# Power_Tree.net
KiCad netlist of a schematic drawn in Altium Designer
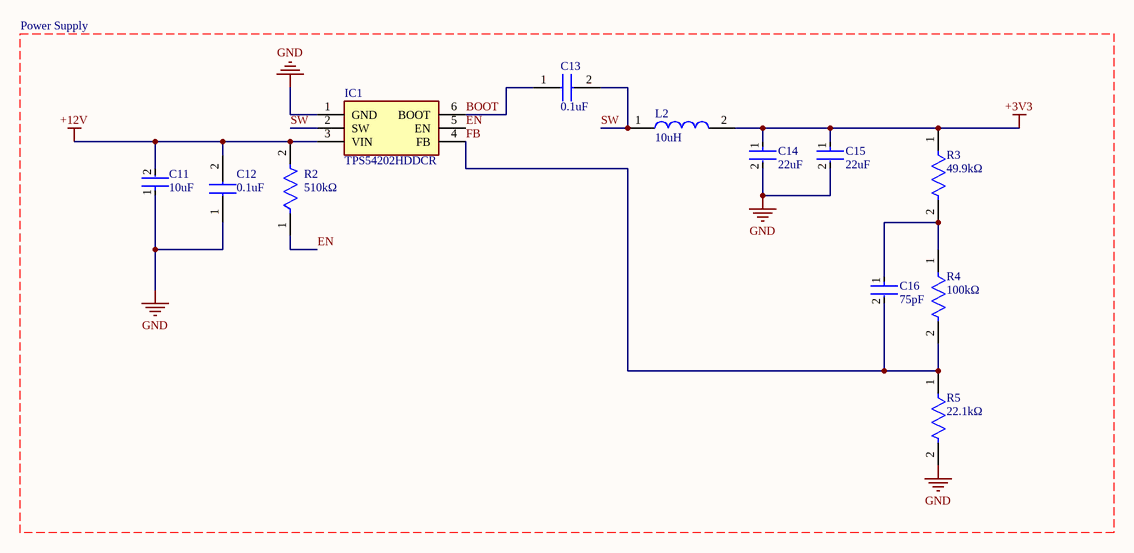
[diagram p0: Power_Tree.SchDoc]

(export (version "E")
  (design (tool "Eeschema 10.0.6"))
  (components
    (comp (ref "C11")
      (value "10uF")
      (footprint "FP-GRT31C-0_2-IPC_A")
      (description "Multi-Layer Ceramic Capacitor 10uF 50V X5R ±10% 1206 Emboss T/R")
      (fields (field (name "TOLERANCE") "10%"))
      (libsource (lib "Altium Content Vault") (part "02cd4be3c70576c341d710602a673aa"))
    )
    (comp (ref "C12")
      (value "0.1uF")
      (footprint "SamacSys:C0805")
      (description "Capacitor")
      (fields
        (field (name "MANUFACTURER_PART_NUMBER") "C0805C104K6RACTU")
        (field (name "MOUSER PART NUMBER") "80-C0805C104K6R")
      )
      (libsource (lib "*") (part "C0805C104K6RACTU"))
    )
    (comp (ref "C13")
      (value "0.1uF")
      (footprint "SamacSys:C0805")
      (description "Capacitor")
      (fields
        (field (name "MANUFACTURER_PART_NUMBER") "C0805C104K6RACTU")
        (field (name "MOUSER PART NUMBER") "80-C0805C104K6R")
      )
      (libsource (lib "*") (part "C0805C104K6RACTU"))
    )
    (comp (ref "C14")
      (value "22uF")
      (footprint "FP-1206-L_3_2_0_3-W_1_6_0-IPC_A")
      (description "None")
      (fields (field (name "TOLERANCE") "20%"))
      (libsource (lib "Altium Content Vault") (part "11868f565c42a9108669ba33697ecf6"))
    )
    (comp (ref "C15")
      (value "22uF")
      (footprint "FP-1206-L_3_2_0_3-W_1_6_0-IPC_A")
      (description "None")
      (fields (field (name "TOLERANCE") "20%"))
      (libsource (lib "Altium Content Vault") (part "11868f565c42a9108669ba33697ecf6"))
    )
    (comp (ref "C16")
      (value "75pF")
      (footprint "FP-C1206C-EB-MFG")
      (description "CAP CER 75PF 50V NP0 1206")
      (fields (field (name "TOLERANCE") "0.05") (field (name "MANUFACTURER PART NUMBER") "C1206C750J5GACTU"))
      (libsource (lib "Altium Content Vault") (part "b4654b650e69147ec39a6b967a45e02"))
    )
    (comp (ref "IC1")
      (value "TPS54202HDDCR")
      (footprint "SamacSys:SOT95P280X110-6N")
      (description "Integrated Circuit")
      (fields (field (name "MOUSER PART NUMBER") "595-TPS54202HDDCR"))
      (libsource (lib "*") (part "TPS54202HDDCR"))
    )
    (comp (ref "L2")
      (value "10uH")
      (footprint "SamacSys:SRN6045_1")
      (description "Inductor")
      (fields
        (field (name "MANUFACTURER_PART_NUMBER") "SRN6045-100M")
        (field (name "MOUSER PART NUMBER") "652-SRN6045-100M")
      )
      (libsource (lib "*") (part "SRN6045-100M"))
    )
    (comp (ref "R2")
      (value "510kΩ")
      (footprint "FP-CRCW0805-e3-IPC_B")
      (description "RES Thick Film, 510kΩ, 1%, 0.125W, 100ppm/°C, 0805")
      (fields (field (name "TOLERANCE") "1%"))
      (libsource (lib "Altium Content Vault") (part "1029c3af85768c4190bb7ad29bc67b5"))
    )
    (comp (ref "R3")
      (value "49.9kΩ")
      (footprint "FP-CRCW0805-e3-IPC_C")
      (description "RES Thick Film, 49.9kΩ, 1%, 0.125W, 100ppm/°C, 0805")
      (fields (field (name "TOLERANCE") "1%"))
      (libsource (lib "Altium Content Vault") (part "1029c3af85768c4190bb7ad29bc67b5"))
    )
    (comp (ref "R4")
      (value "100kΩ")
      (footprint "FP-CRCW0805-e3-MFG")
      (description "RES Thick Film, 100kΩ, 1%, 0.125W, 100ppm/°C, 0805")
      (fields (field (name "TOLERANCE") "1%"))
      (libsource (lib "Altium Content Vault") (part "1029c3af85768c4190bb7ad29bc67b5"))
    )
    (comp (ref "R5")
      (value "22.1kΩ")
      (footprint "FP-CRCW0805-e3-IPC_C")
      (description "RES Thick Film, 22.1kΩ, 1%, 0.125W, 100ppm/°C, 0805")
      (fields (field (name "TOLERANCE") "1%"))
      (libsource (lib "Altium Content Vault") (part "1029c3af85768c4190bb7ad29bc67b5"))
    )
  )
  (nets
    (net (code "1") (name "+3V3") (class "Default")
      (node (ref "C14") (pin "1") (pinfunction "1_1") (pintype "passive"))
      (node (ref "C15") (pin "1") (pinfunction "1_1") (pintype "passive"))
      (node (ref "L2") (pin "2") (pinfunction "2_2") (pintype "passive"))
      (node (ref "R3") (pin "1") (pinfunction "1_1") (pintype "passive"))
    )
    (net (code "2") (name "+12V") (class "Default")
      (node (ref "C11") (pin "2") (pinfunction "2_2") (pintype "passive"))
      (node (ref "C12") (pin "2") (pinfunction "2_2") (pintype "passive"))
      (node (ref "IC1") (pin "3") (pinfunction "VIN_3") (pintype "passive"))
      (node (ref "R2") (pin "2") (pinfunction "2_2") (pintype "passive"))
    )
    (net (code "3") (name "/BOOT") (class "Default")
      (node (ref "C13") (pin "1") (pinfunction "1_1") (pintype "passive"))
      (node (ref "IC1") (pin "6") (pinfunction "BOOT_6") (pintype "passive"))
    )
    (net (code "4") (name "/EN") (class "Default")
      (node (ref "IC1") (pin "5") (pinfunction "EN_5") (pintype "passive"))
      (node (ref "R2") (pin "1") (pinfunction "1_1") (pintype "passive"))
    )
    (net (code "5") (name "/FB") (class "Default")
      (node (ref "C16") (pin "2") (pinfunction "2_2") (pintype "passive"))
      (node (ref "IC1") (pin "4") (pinfunction "FB_4") (pintype "passive"))
      (node (ref "R4") (pin "2") (pinfunction "2_2") (pintype "passive"))
      (node (ref "R5") (pin "1") (pinfunction "1_1") (pintype "passive"))
    )
    (net (code "6") (name "/SW") (class "Default")
      (node (ref "C13") (pin "2") (pinfunction "2_2") (pintype "passive"))
      (node (ref "IC1") (pin "2") (pinfunction "SW_2") (pintype "passive"))
      (node (ref "L2") (pin "1") (pinfunction "1_1") (pintype "passive"))
    )
    (net (code "7") (name "GND") (class "Default")
      (node (ref "C11") (pin "1") (pinfunction "1_1") (pintype "passive"))
      (node (ref "C12") (pin "1") (pinfunction "1_1") (pintype "passive"))
      (node (ref "C14") (pin "2") (pinfunction "2_2") (pintype "passive"))
      (node (ref "C15") (pin "2") (pinfunction "2_2") (pintype "passive"))
      (node (ref "IC1") (pin "1") (pinfunction "GND_1") (pintype "passive"))
      (node (ref "R5") (pin "2") (pinfunction "2_2") (pintype "passive"))
    )
    (net (code "8") (name "Net-(C16-Pad1)") (class "Default")
      (node (ref "C16") (pin "1") (pinfunction "1_1") (pintype "passive"))
      (node (ref "R3") (pin "2") (pinfunction "2_2") (pintype "passive"))
      (node (ref "R4") (pin "1") (pinfunction "1_1") (pintype "passive"))
    )
  )
)
